# Connectors.net
KiCad netlist of a schematic drawn in Altium Designer
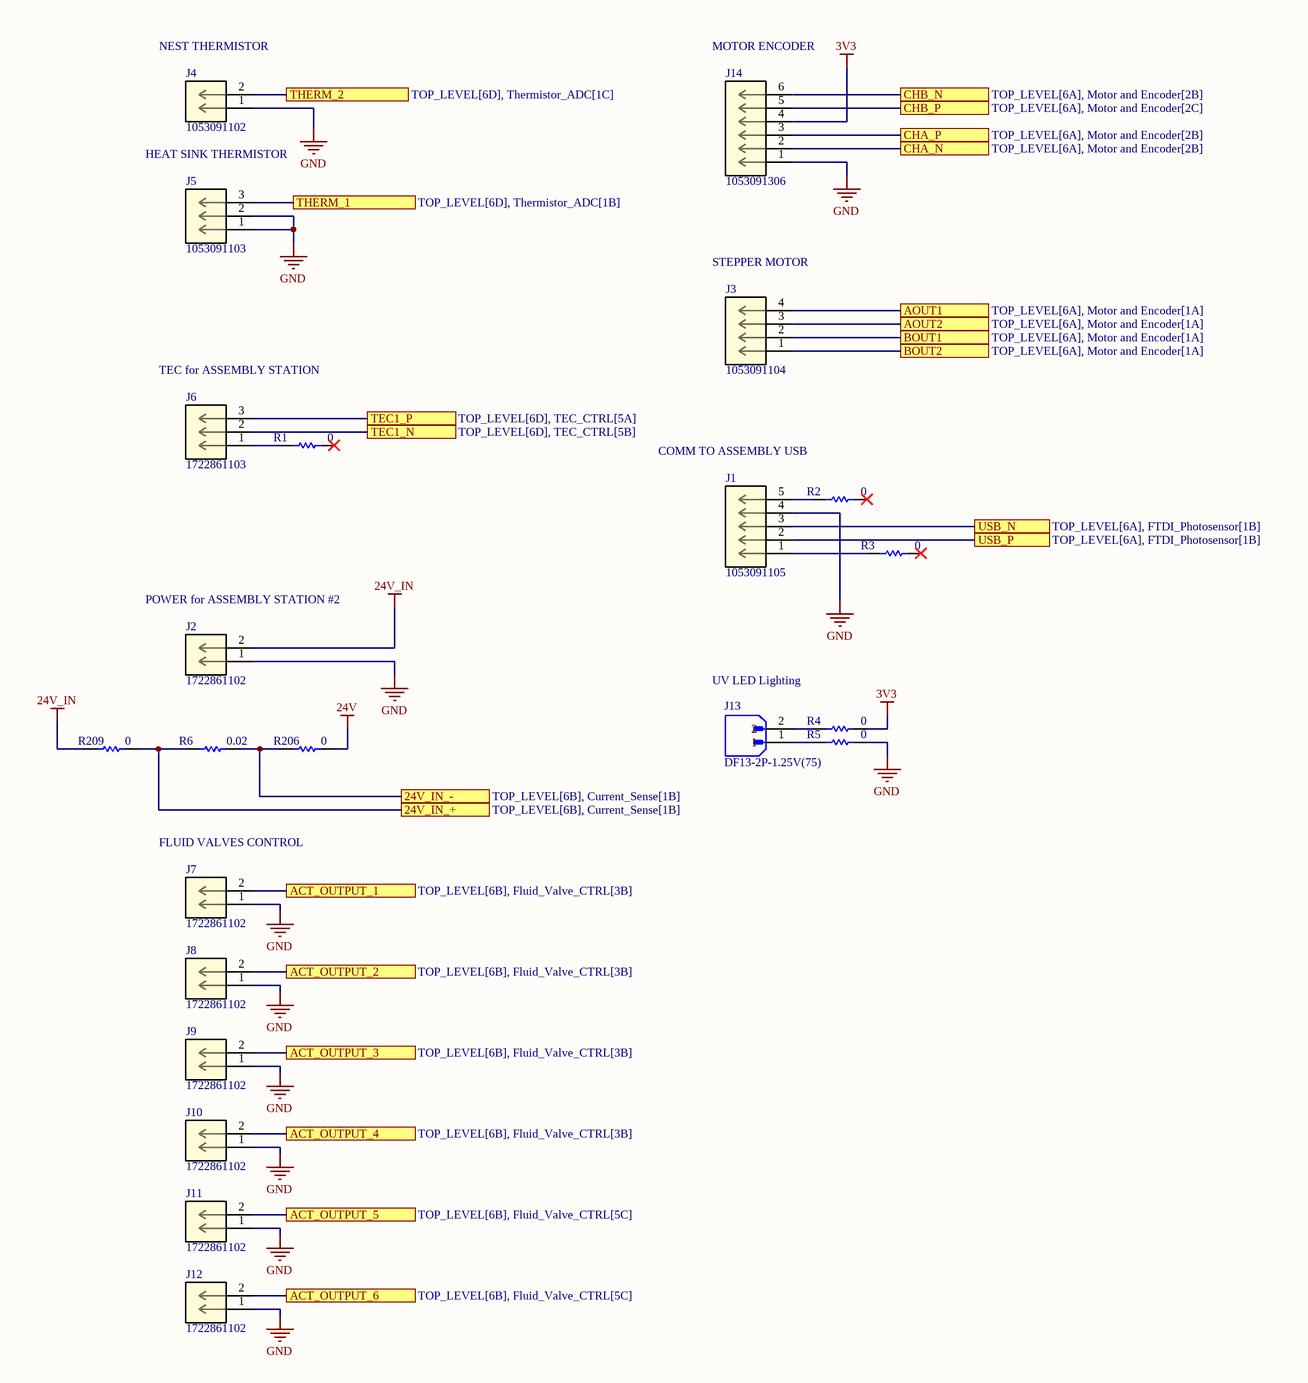
[diagram p0: Connectors.SchDoc]

(export (version "E")
  (design (tool "Eeschema 10.0.6"))
  (components
    (comp (ref "J1")
      (value "1053091105")
      (footprint "1053091105")
      (fields (field (name "COPYRIGHT") "Copyright (C) 2025 Ultra Librarian. All rights reserved."))
      (libsource (lib "Avery Altium Llibrary") (part "1053091105"))
    )
    (comp (ref "J2")
      (value "1722861102")
      (footprint "1722861102")
      (fields (field (name "COPYRIGHT") "Copyright (C) 2025 Ultra Librarian. All rights reserved."))
      (libsource (lib "Avery Altium Llibrary") (part "1722861102"))
    )
    (comp (ref "J3")
      (value "1053091104")
      (footprint "1053091104")
      (fields (field (name "COPYRIGHT") "Copyright (C) 2025 Ultra Librarian. All rights reserved."))
      (libsource (lib "Avery Altium Llibrary") (part "1053091104"))
    )
    (comp (ref "J4")
      (value "1053091102")
      (footprint "1053091102")
      (fields (field (name "COPYRIGHT") "Copyright (C) 2025 Ultra Librarian. All rights reserved."))
      (libsource (lib "Avery Altium Llibrary") (part "1053091102"))
    )
    (comp (ref "J5")
      (value "1053091103")
      (footprint "1053091103")
      (fields (field (name "COPYRIGHT") "Copyright (C) 2025 Ultra Librarian. All rights reserved."))
      (libsource (lib "Avery Altium Llibrary") (part "1053091103"))
    )
    (comp (ref "J6")
      (value "1722861103")
      (footprint "1722861103")
      (fields (field (name "COPYRIGHT") "Copyright (C) 2025 Ultra Librarian. All rights reserved."))
      (libsource (lib "Avery Altium Llibrary") (part "1722861103"))
    )
    (comp (ref "J7")
      (value "1722861102")
      (footprint "1722861102")
      (fields (field (name "COPYRIGHT") "Copyright (C) 2025 Ultra Librarian. All rights reserved."))
      (libsource (lib "Avery Altium Llibrary") (part "1722861102"))
    )
    (comp (ref "J8")
      (value "1722861102")
      (footprint "1722861102")
      (fields (field (name "COPYRIGHT") "Copyright (C) 2025 Ultra Librarian. All rights reserved."))
      (libsource (lib "Avery Altium Llibrary") (part "1722861102"))
    )
    (comp (ref "J9")
      (value "1722861102")
      (footprint "1722861102")
      (fields (field (name "COPYRIGHT") "Copyright (C) 2025 Ultra Librarian. All rights reserved."))
      (libsource (lib "Avery Altium Llibrary") (part "1722861102"))
    )
    (comp (ref "J10")
      (value "1722861102")
      (footprint "1722861102")
      (fields (field (name "COPYRIGHT") "Copyright (C) 2025 Ultra Librarian. All rights reserved."))
      (libsource (lib "Avery Altium Llibrary") (part "1722861102"))
    )
    (comp (ref "J11")
      (value "1722861102")
      (footprint "1722861102")
      (fields (field (name "COPYRIGHT") "Copyright (C) 2025 Ultra Librarian. All rights reserved."))
      (libsource (lib "Avery Altium Llibrary") (part "1722861102"))
    )
    (comp (ref "J12")
      (value "1722861102")
      (footprint "1722861102")
      (fields (field (name "COPYRIGHT") "Copyright (C) 2025 Ultra Librarian. All rights reserved."))
      (libsource (lib "Avery Altium Llibrary") (part "1722861102"))
    )
    (comp (ref "J13")
      (value "DF13-2P-1.25V(75)")
      (footprint "DF13-2P-1.25V(75)")
      (description "Connector Header Surface Mount 2 position 0.049 (1.25mm)")
      (fields (field (name "MF") "Hirose Electric Co Ltd"))
      (libsource (lib "Avery Altium Llibrary") (part "DF13-2P-1.25V(75)"))
    )
    (comp (ref "J14")
      (value "1053091306")
      (footprint "1053091306")
      (fields (field (name "COPYRIGHT") "Copyright (C) 2025 Ultra Librarian. All rights reserved."))
      (libsource (lib "Avery Altium Llibrary") (part "1053091306"))
    )
    (comp (ref "R1")
      (value "0")
      (footprint "DEFAULT_RESISTOR_0805")
      (description "RES 0 OHM JUMPER 1/8W 0805")
      (fields (field (name "POWER") "1/8W") (field (name "Comment") "RC0805JR-070RL"))
      (libsource (lib "Avery Altium Llibrary") (part "RC0805JR-070RL"))
    )
    (comp (ref "R2")
      (value "0")
      (footprint "DEFAULT_RESISTOR_0805")
      (description "RES 0 OHM JUMPER 1/8W 0805")
      (fields (field (name "POWER") "1/8W") (field (name "Comment") "RC0805JR-070RL"))
      (libsource (lib "Avery Altium Llibrary") (part "RC0805JR-070RL"))
    )
    (comp (ref "R3")
      (value "0")
      (footprint "DEFAULT_RESISTOR_0805")
      (description "RES 0 OHM JUMPER 1/8W 0805")
      (fields (field (name "POWER") "1/8W") (field (name "Comment") "RC0805JR-070RL"))
      (libsource (lib "Avery Altium Llibrary") (part "RC0805JR-070RL"))
    )
    (comp (ref "R4")
      (value "0")
      (footprint "DEFAULT_RESISTOR_0805")
      (description "RES 0 OHM JUMPER 1/8W 0805")
      (fields (field (name "POWER") "1/8W") (field (name "Comment") "RC0805JR-070RL"))
      (libsource (lib "Avery Altium Llibrary") (part "RC0805JR-070RL"))
    )
    (comp (ref "R5")
      (value "0")
      (footprint "DEFAULT_RESISTOR_0805")
      (description "RES 0 OHM JUMPER 1/8W 0805")
      (fields (field (name "POWER") "1/8W") (field (name "Comment") "RC0805JR-070RL"))
      (libsource (lib "Avery Altium Llibrary") (part "RC0805JR-070RL"))
    )
    (comp (ref "R6")
      (value "0.02")
      (footprint "DEFAULT_RESISTOR_0805")
      (description "RES 0.02 OHM 0.5% 1/2W 0805")
      (fields (field (name "POWER") "1/2W") (field (name "TOLERANCE") "0.5%"))
      (libsource (lib "Avery Altium Llibrary") (part "ERJ-6CWDR020V"))
    )
    (comp (ref "R206")
      (value "0")
      (footprint "DEFAULT_RESISTOR_0805")
      (description "RES 0 OHM JUMPER 1/8W 0805")
      (fields (field (name "POWER") "1/8W") (field (name "Comment") "RC0805JR-070RL"))
      (libsource (lib "Avery Altium Llibrary") (part "RC0805JR-070RL"))
    )
    (comp (ref "R209")
      (value "0")
      (footprint "DEFAULT_RESISTOR_0805")
      (description "RES 0 OHM JUMPER 1/8W 0805")
      (fields (field (name "POWER") "1/8W") (field (name "Comment") "RC0805JR-070RL"))
      (libsource (lib "Avery Altium Llibrary") (part "RC0805JR-070RL"))
    )
  )
  (nets
    (net (code "1") (name "/24V_IN_+") (class "Default")
      (node (ref "R209") (pin "1") (pinfunction "1_1") (pintype "passive"))
      (node (ref "R6") (pin "2") (pinfunction "2_2") (pintype "passive"))
    )
    (net (code "2") (name "/24V_IN_-") (class "Default")
      (node (ref "R206") (pin "2") (pinfunction "2_2") (pintype "passive"))
      (node (ref "R6") (pin "1") (pinfunction "1_1") (pintype "passive"))
    )
    (net (code "3") (name "/ACT_OUTPUT_1") (class "Default")
      (node (ref "J7") (pin "2") (pinfunction "2_2") (pintype "passive"))
    )
    (net (code "4") (name "/ACT_OUTPUT_2") (class "Default")
      (node (ref "J8") (pin "2") (pinfunction "2_2") (pintype "passive"))
    )
    (net (code "5") (name "/ACT_OUTPUT_3") (class "Default")
      (node (ref "J9") (pin "2") (pinfunction "2_2") (pintype "passive"))
    )
    (net (code "6") (name "/ACT_OUTPUT_4") (class "Default")
      (node (ref "J10") (pin "2") (pinfunction "2_2") (pintype "passive"))
    )
    (net (code "7") (name "/ACT_OUTPUT_5") (class "Default")
      (node (ref "J11") (pin "2") (pinfunction "2_2") (pintype "passive"))
    )
    (net (code "8") (name "/ACT_OUTPUT_6") (class "Default")
      (node (ref "J12") (pin "2") (pinfunction "2_2") (pintype "passive"))
    )
    (net (code "9") (name "/AOUT1") (class "Default")
      (node (ref "J3") (pin "4") (pinfunction "4_4") (pintype "passive"))
    )
    (net (code "10") (name "/AOUT2") (class "Default")
      (node (ref "J3") (pin "3") (pinfunction "3_3") (pintype "passive"))
    )
    (net (code "11") (name "/BOUT1") (class "Default")
      (node (ref "J3") (pin "2") (pinfunction "2_2") (pintype "passive"))
    )
    (net (code "12") (name "/BOUT2") (class "Default")
      (node (ref "J3") (pin "1") (pinfunction "1_1") (pintype "passive"))
    )
    (net (code "13") (name "/CHA_N") (class "Default")
      (node (ref "J14") (pin "2") (pinfunction "2_2") (pintype "passive"))
    )
    (net (code "14") (name "/CHA_P") (class "Default")
      (node (ref "J14") (pin "3") (pinfunction "3_3") (pintype "passive"))
    )
    (net (code "15") (name "/CHB_N") (class "Default")
      (node (ref "J14") (pin "6") (pinfunction "6_6") (pintype "passive"))
    )
    (net (code "16") (name "/CHB_P") (class "Default")
      (node (ref "J14") (pin "5") (pinfunction "5_5") (pintype "passive"))
    )
    (net (code "17") (name "/TEC1_N") (class "Default")
      (node (ref "J6") (pin "2") (pinfunction "2_2") (pintype "passive"))
    )
    (net (code "18") (name "/TEC1_P") (class "Default")
      (node (ref "J6") (pin "3") (pinfunction "3_3") (pintype "passive"))
    )
    (net (code "19") (name "/THERM_1") (class "Default")
      (node (ref "J5") (pin "3") (pinfunction "3_3") (pintype "passive"))
    )
    (net (code "20") (name "/THERM_2") (class "Default")
      (node (ref "J4") (pin "2") (pinfunction "2_2") (pintype "passive"))
    )
    (net (code "21") (name "/USB_N") (class "Default")
      (node (ref "J1") (pin "3") (pinfunction "3_3") (pintype "passive"))
    )
    (net (code "22") (name "/USB_P") (class "Default")
      (node (ref "J1") (pin "2") (pinfunction "2_2") (pintype "passive"))
    )
    (net (code "23") (name "3V3") (class "Default")
      (node (ref "J14") (pin "4") (pinfunction "4_4") (pintype "passive"))
      (node (ref "R4") (pin "1") (pinfunction "1_1") (pintype "passive"))
    )
    (net (code "24") (name "24V") (class "Default")
      (node (ref "R206") (pin "1") (pinfunction "1_1") (pintype "passive"))
    )
    (net (code "25") (name "24V_IN") (class "Default")
      (node (ref "J2") (pin "2") (pinfunction "2_2") (pintype "passive"))
      (node (ref "R209") (pin "2") (pinfunction "2_2") (pintype "passive"))
    )
    (net (code "26") (name "GND") (class "Default")
      (node (ref "J1") (pin "4") (pinfunction "4_4") (pintype "passive"))
      (node (ref "J10") (pin "1") (pinfunction "1_1") (pintype "passive"))
      (node (ref "J11") (pin "1") (pinfunction "1_1") (pintype "passive"))
      (node (ref "J12") (pin "1") (pinfunction "1_1") (pintype "passive"))
      (node (ref "J14") (pin "1") (pinfunction "1_1") (pintype "passive"))
      (node (ref "J2") (pin "1") (pinfunction "1_1") (pintype "passive"))
      (node (ref "J4") (pin "1") (pinfunction "1_1") (pintype "passive"))
      (node (ref "J5") (pin "1") (pinfunction "1_1") (pintype "passive"))
      (node (ref "J5") (pin "2") (pinfunction "2_2") (pintype "passive"))
      (node (ref "J7") (pin "1") (pinfunction "1_1") (pintype "passive"))
      (node (ref "J8") (pin "1") (pinfunction "1_1") (pintype "passive"))
      (node (ref "J9") (pin "1") (pinfunction "1_1") (pintype "passive"))
      (node (ref "R5") (pin "1") (pinfunction "1_1") (pintype "passive"))
    )
    (net (code "27") (name "Net-(J1-Pad1)") (class "Default")
      (node (ref "J1") (pin "1") (pinfunction "1_1") (pintype "passive"))
      (node (ref "R3") (pin "2") (pinfunction "2_2") (pintype "passive"))
    )
    (net (code "28") (name "Net-(J1-Pad5)") (class "Default")
      (node (ref "J1") (pin "5") (pinfunction "5_5") (pintype "passive"))
      (node (ref "R2") (pin "2") (pinfunction "2_2") (pintype "passive"))
    )
    (net (code "29") (name "Net-(J6-Pad1)") (class "Default")
      (node (ref "J6") (pin "1") (pinfunction "1_1") (pintype "passive"))
      (node (ref "R1") (pin "2") (pinfunction "2_2") (pintype "passive"))
    )
    (net (code "30") (name "Net-(J13-Pad1)") (class "Default")
      (node (ref "J13") (pin "1") (pinfunction "1_1") (pintype "passive"))
      (node (ref "R5") (pin "2") (pinfunction "2_2") (pintype "passive"))
    )
    (net (code "31") (name "Net-(J13-Pad2)") (class "Default")
      (node (ref "J13") (pin "2") (pinfunction "2_2") (pintype "passive"))
      (node (ref "R4") (pin "2") (pinfunction "2_2") (pintype "passive"))
    )
    (net (code "32") (name "unconnected-(R1-Pad1)") (class "Default")
      (node (ref "R1") (pin "1") (pinfunction "1_1") (pintype "passive+no_connect"))
    )
    (net (code "33") (name "unconnected-(R2-Pad1)") (class "Default")
      (node (ref "R2") (pin "1") (pinfunction "1_1") (pintype "passive+no_connect"))
    )
    (net (code "34") (name "unconnected-(R3-Pad1)") (class "Default")
      (node (ref "R3") (pin "1") (pinfunction "1_1") (pintype "passive+no_connect"))
    )
  )
)
